# blink-bot.net
KiCad netlist of a schematic drawn in EasyEDA
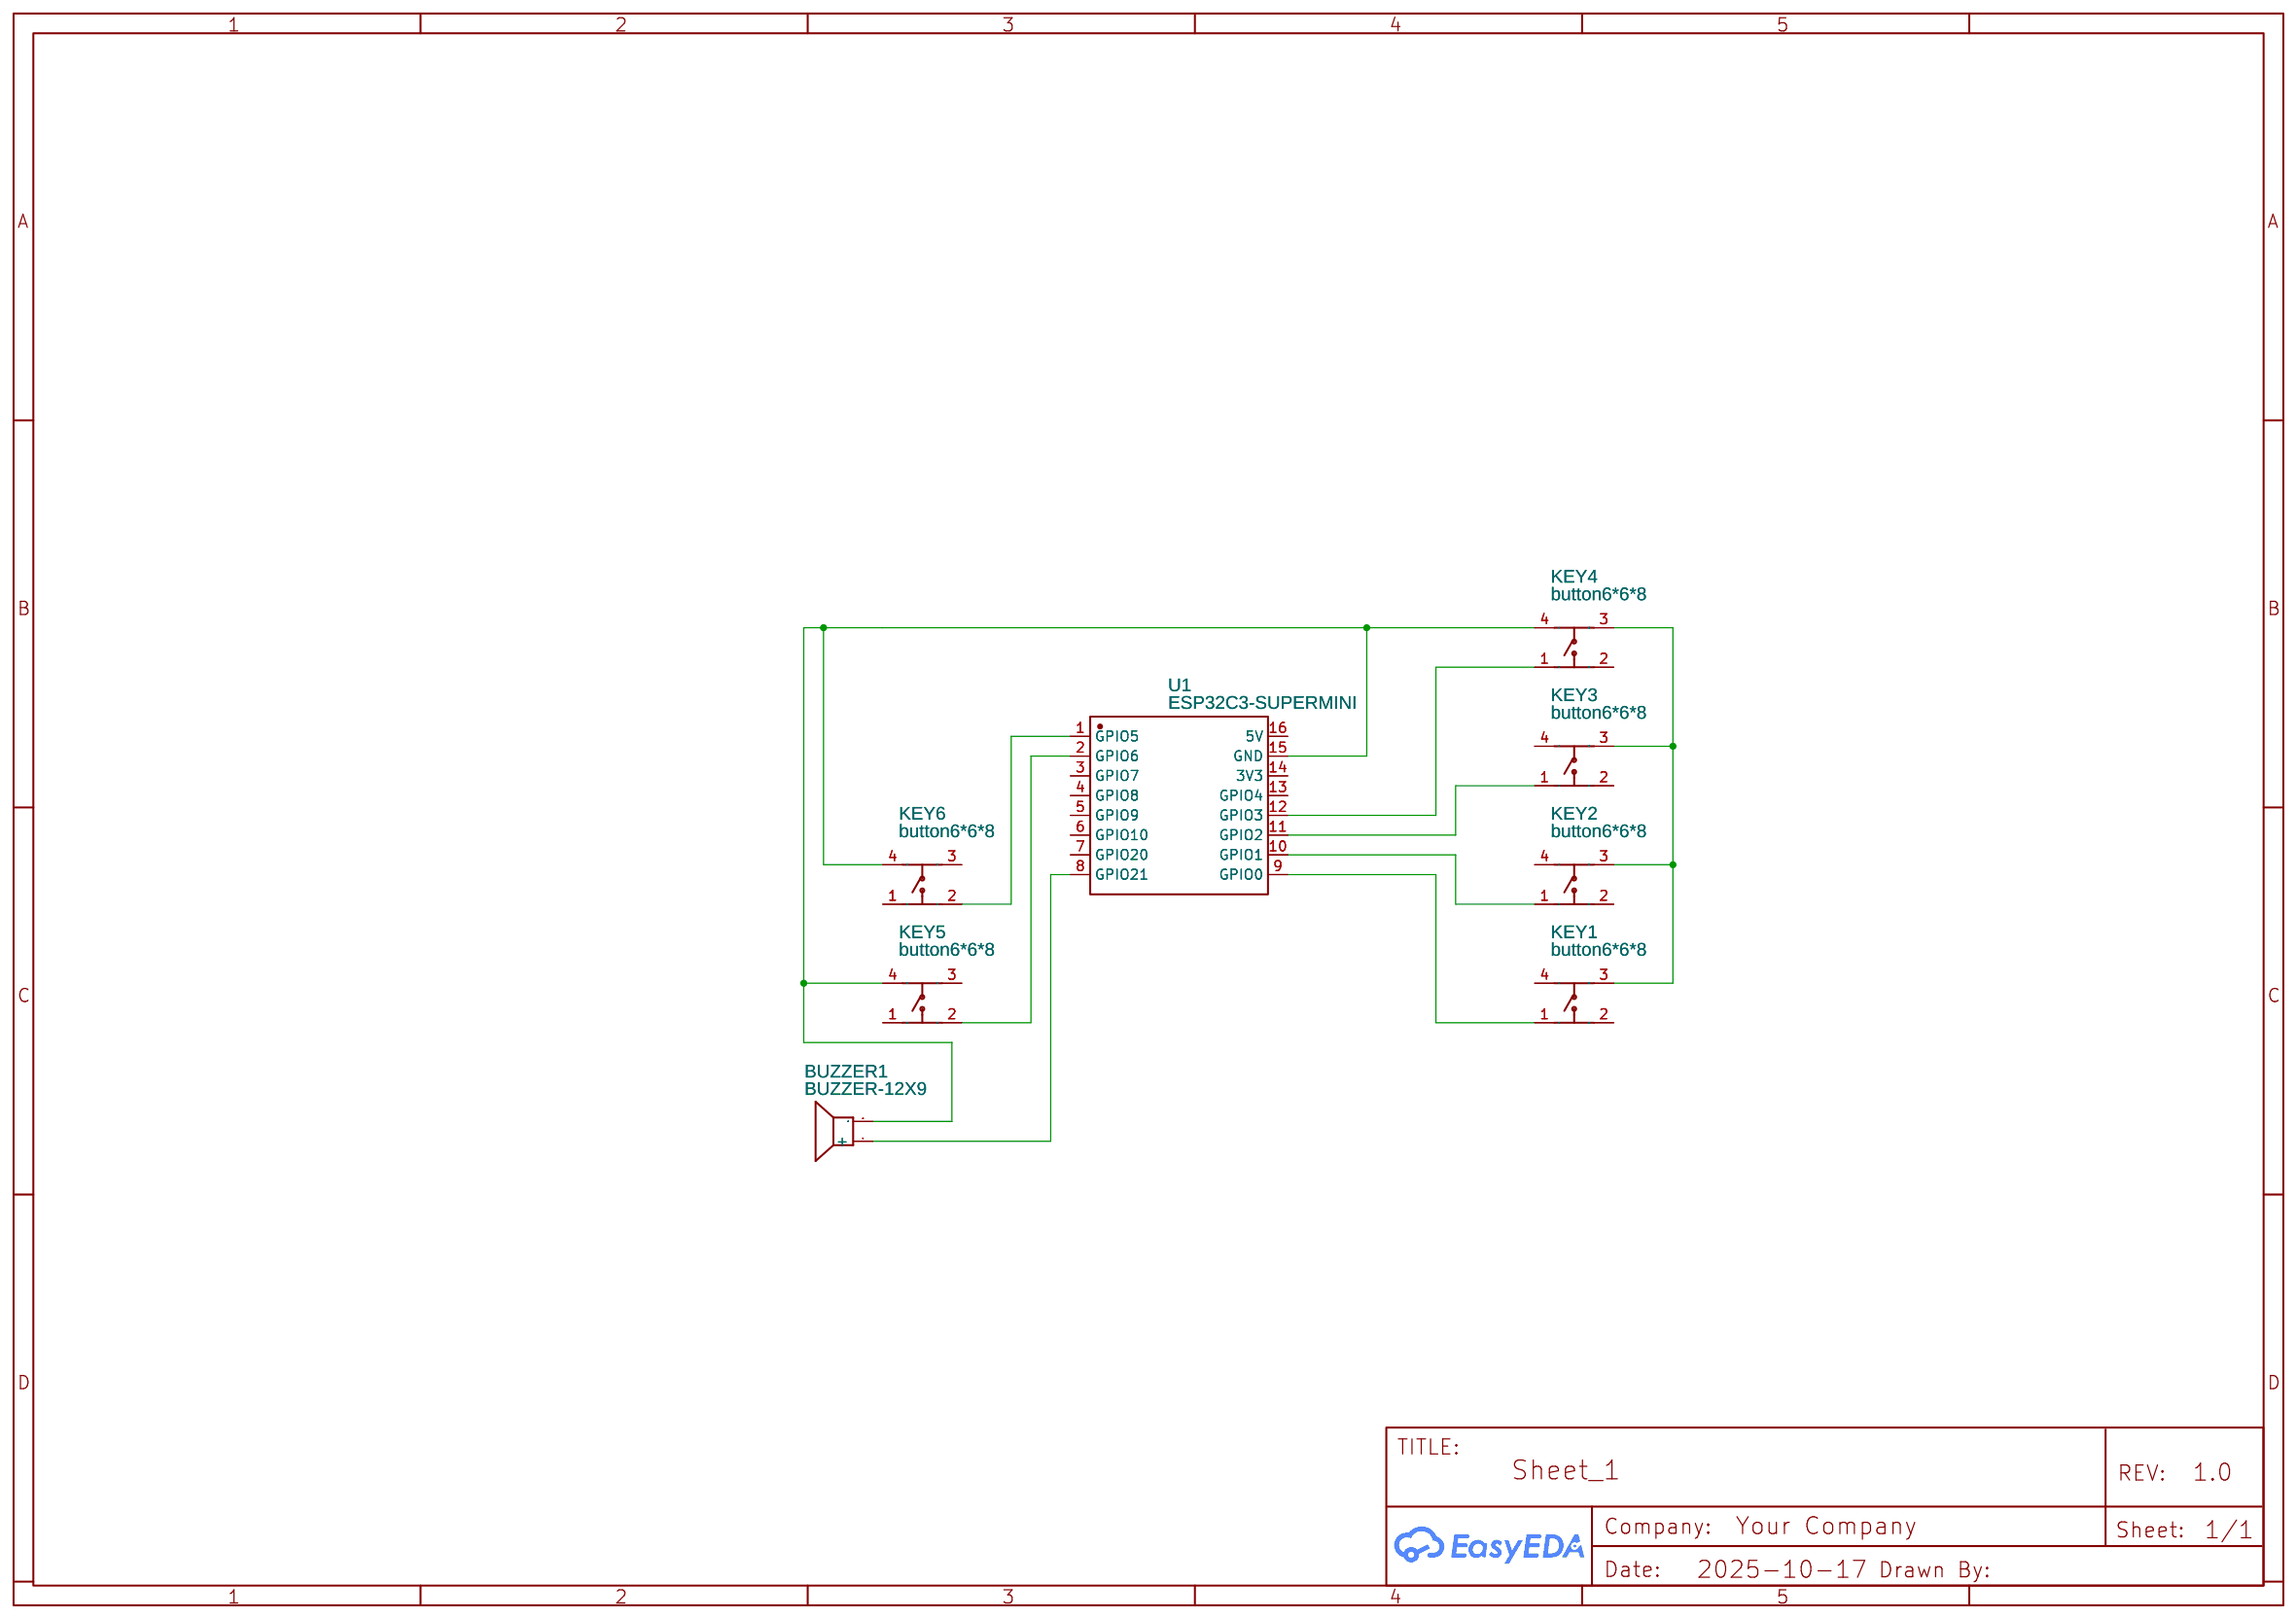
[diagram p0: schematic sheet]

(export (version "E")
  (design (tool "Eeschema 10.0.6"))
  (components
    (comp (ref "BUZZER1")
      (value "BUZZER-12X9")
      (fields (field (name "Manufacturer Part") "buzzer-12X9"))
      (libsource (lib "") (part "BUZZER-12X9"))
    )
    (comp (ref "KEY1")
      (value "button6*6*8")
      (fields (field (name "Manufacturer") "ReliaPro"))
      (libsource (lib "") (part "button6*6*8"))
    )
    (comp (ref "KEY2")
      (value "button6*6*8")
      (fields (field (name "Manufacturer") "ReliaPro"))
      (libsource (lib "") (part "button6*6*8"))
    )
    (comp (ref "KEY3")
      (value "button6*6*8")
      (fields (field (name "Manufacturer") "ReliaPro"))
      (libsource (lib "") (part "button6*6*8"))
    )
    (comp (ref "KEY4")
      (value "button6*6*8")
      (fields (field (name "Manufacturer") "ReliaPro"))
      (libsource (lib "") (part "button6*6*8"))
    )
    (comp (ref "KEY5")
      (value "button6*6*8")
      (fields (field (name "Manufacturer") "ReliaPro"))
      (libsource (lib "") (part "button6*6*8"))
    )
    (comp (ref "KEY6")
      (value "button6*6*8")
      (fields (field (name "Manufacturer") "ReliaPro"))
      (libsource (lib "") (part "button6*6*8"))
    )
    (comp (ref "U1")
      (value "ESP32C3-SUPERMINI")
      (fields (field (name "Manufacturer Part") "ESP32C3-SuperMini"))
      (libsource (lib "") (part "ESP32C3-SUPERMINI"))
    )
  )
  (nets
    (net (code "1") (name "Net-(BUZZER1-+)") (class "Default")
      (node (ref "BUZZER1") (pin "1") (pinfunction "+_1") (pintype "unspecified"))
      (node (ref "U1") (pin "8") (pinfunction "GPIO21_8") (pintype "unspecified"))
    )
    (net (code "2") (name "Net-(KEY1-Pad3)") (class "Default")
      (node (ref "KEY1") (pin "3") (pinfunction "3_3") (pintype "unspecified"))
      (node (ref "KEY2") (pin "3") (pinfunction "3_3") (pintype "unspecified"))
      (node (ref "KEY3") (pin "3") (pinfunction "3_3") (pintype "unspecified"))
      (node (ref "KEY4") (pin "3") (pinfunction "3_3") (pintype "unspecified"))
    )
    (net (code "3") (name "Net-(U1-GND)") (class "Default")
      (node (ref "BUZZER1") (pin "2") (pinfunction "2_2") (pintype "unspecified"))
      (node (ref "KEY4") (pin "4") (pinfunction "4_4") (pintype "unspecified"))
      (node (ref "KEY5") (pin "4") (pinfunction "4_4") (pintype "unspecified"))
      (node (ref "KEY6") (pin "4") (pinfunction "4_4") (pintype "unspecified"))
      (node (ref "U1") (pin "15") (pinfunction "GND_15") (pintype "unspecified"))
    )
    (net (code "4") (name "Net-(U1-GPIO0)") (class "Default")
      (node (ref "KEY1") (pin "1") (pinfunction "1_1") (pintype "unspecified"))
      (node (ref "U1") (pin "9") (pinfunction "GPIO0_9") (pintype "unspecified"))
    )
    (net (code "5") (name "Net-(U1-GPIO1)") (class "Default")
      (node (ref "KEY2") (pin "1") (pinfunction "1_1") (pintype "unspecified"))
      (node (ref "U1") (pin "10") (pinfunction "GPIO1_10") (pintype "unspecified"))
    )
    (net (code "6") (name "Net-(U1-GPIO2)") (class "Default")
      (node (ref "KEY3") (pin "1") (pinfunction "1_1") (pintype "unspecified"))
      (node (ref "U1") (pin "11") (pinfunction "GPIO2_11") (pintype "unspecified"))
    )
    (net (code "7") (name "Net-(U1-GPIO3)") (class "Default")
      (node (ref "KEY4") (pin "1") (pinfunction "1_1") (pintype "unspecified"))
      (node (ref "U1") (pin "12") (pinfunction "GPIO3_12") (pintype "unspecified"))
    )
    (net (code "8") (name "Net-(U1-GPIO5)") (class "Default")
      (node (ref "KEY6") (pin "2") (pinfunction "2_2") (pintype "unspecified"))
      (node (ref "U1") (pin "1") (pinfunction "GPIO5_1") (pintype "unspecified"))
    )
    (net (code "9") (name "Net-(U1-GPIO6)") (class "Default")
      (node (ref "KEY5") (pin "2") (pinfunction "2_2") (pintype "unspecified"))
      (node (ref "U1") (pin "2") (pinfunction "GPIO6_2") (pintype "unspecified"))
    )
    (net (code "10") (name "unconnected-(KEY1-Pad2)") (class "Default")
      (node (ref "KEY1") (pin "2") (pinfunction "2_2") (pintype "unspecified"))
    )
    (net (code "11") (name "unconnected-(KEY1-Pad4)") (class "Default")
      (node (ref "KEY1") (pin "4") (pinfunction "4_4") (pintype "unspecified"))
    )
    (net (code "12") (name "unconnected-(KEY2-Pad2)") (class "Default")
      (node (ref "KEY2") (pin "2") (pinfunction "2_2") (pintype "unspecified"))
    )
    (net (code "13") (name "unconnected-(KEY2-Pad4)") (class "Default")
      (node (ref "KEY2") (pin "4") (pinfunction "4_4") (pintype "unspecified"))
    )
    (net (code "14") (name "unconnected-(KEY3-Pad2)") (class "Default")
      (node (ref "KEY3") (pin "2") (pinfunction "2_2") (pintype "unspecified"))
    )
    (net (code "15") (name "unconnected-(KEY3-Pad4)") (class "Default")
      (node (ref "KEY3") (pin "4") (pinfunction "4_4") (pintype "unspecified"))
    )
    (net (code "16") (name "unconnected-(KEY4-Pad2)") (class "Default")
      (node (ref "KEY4") (pin "2") (pinfunction "2_2") (pintype "unspecified"))
    )
    (net (code "17") (name "unconnected-(KEY5-Pad1)") (class "Default")
      (node (ref "KEY5") (pin "1") (pinfunction "1_1") (pintype "unspecified"))
    )
    (net (code "18") (name "unconnected-(KEY5-Pad3)") (class "Default")
      (node (ref "KEY5") (pin "3") (pinfunction "3_3") (pintype "unspecified"))
    )
    (net (code "19") (name "unconnected-(KEY6-Pad1)") (class "Default")
      (node (ref "KEY6") (pin "1") (pinfunction "1_1") (pintype "unspecified"))
    )
    (net (code "20") (name "unconnected-(KEY6-Pad3)") (class "Default")
      (node (ref "KEY6") (pin "3") (pinfunction "3_3") (pintype "unspecified"))
    )
    (net (code "21") (name "unconnected-(U1-3V3-Pad14)") (class "Default")
      (node (ref "U1") (pin "14") (pinfunction "3V3_14") (pintype "unspecified"))
    )
    (net (code "22") (name "unconnected-(U1-5V-Pad16)") (class "Default")
      (node (ref "U1") (pin "16") (pinfunction "5V_16") (pintype "unspecified"))
    )
    (net (code "23") (name "unconnected-(U1-GPIO4-Pad13)") (class "Default")
      (node (ref "U1") (pin "13") (pinfunction "GPIO4_13") (pintype "unspecified"))
    )
    (net (code "24") (name "unconnected-(U1-GPIO7-Pad3)") (class "Default")
      (node (ref "U1") (pin "3") (pinfunction "GPIO7_3") (pintype "unspecified"))
    )
    (net (code "25") (name "unconnected-(U1-GPIO8-Pad4)") (class "Default")
      (node (ref "U1") (pin "4") (pinfunction "GPIO8_4") (pintype "unspecified"))
    )
    (net (code "26") (name "unconnected-(U1-GPIO9-Pad5)") (class "Default")
      (node (ref "U1") (pin "5") (pinfunction "GPIO9_5") (pintype "unspecified"))
    )
    (net (code "27") (name "unconnected-(U1-GPIO10-Pad6)") (class "Default")
      (node (ref "U1") (pin "6") (pinfunction "GPIO10_6") (pintype "unspecified"))
    )
    (net (code "28") (name "unconnected-(U1-GPIO20-Pad7)") (class "Default")
      (node (ref "U1") (pin "7") (pinfunction "GPIO20_7") (pintype "unspecified"))
    )
  )
)
